# Termo-Relay.net
KiCad netlist of a schematic drawn in EAGLE
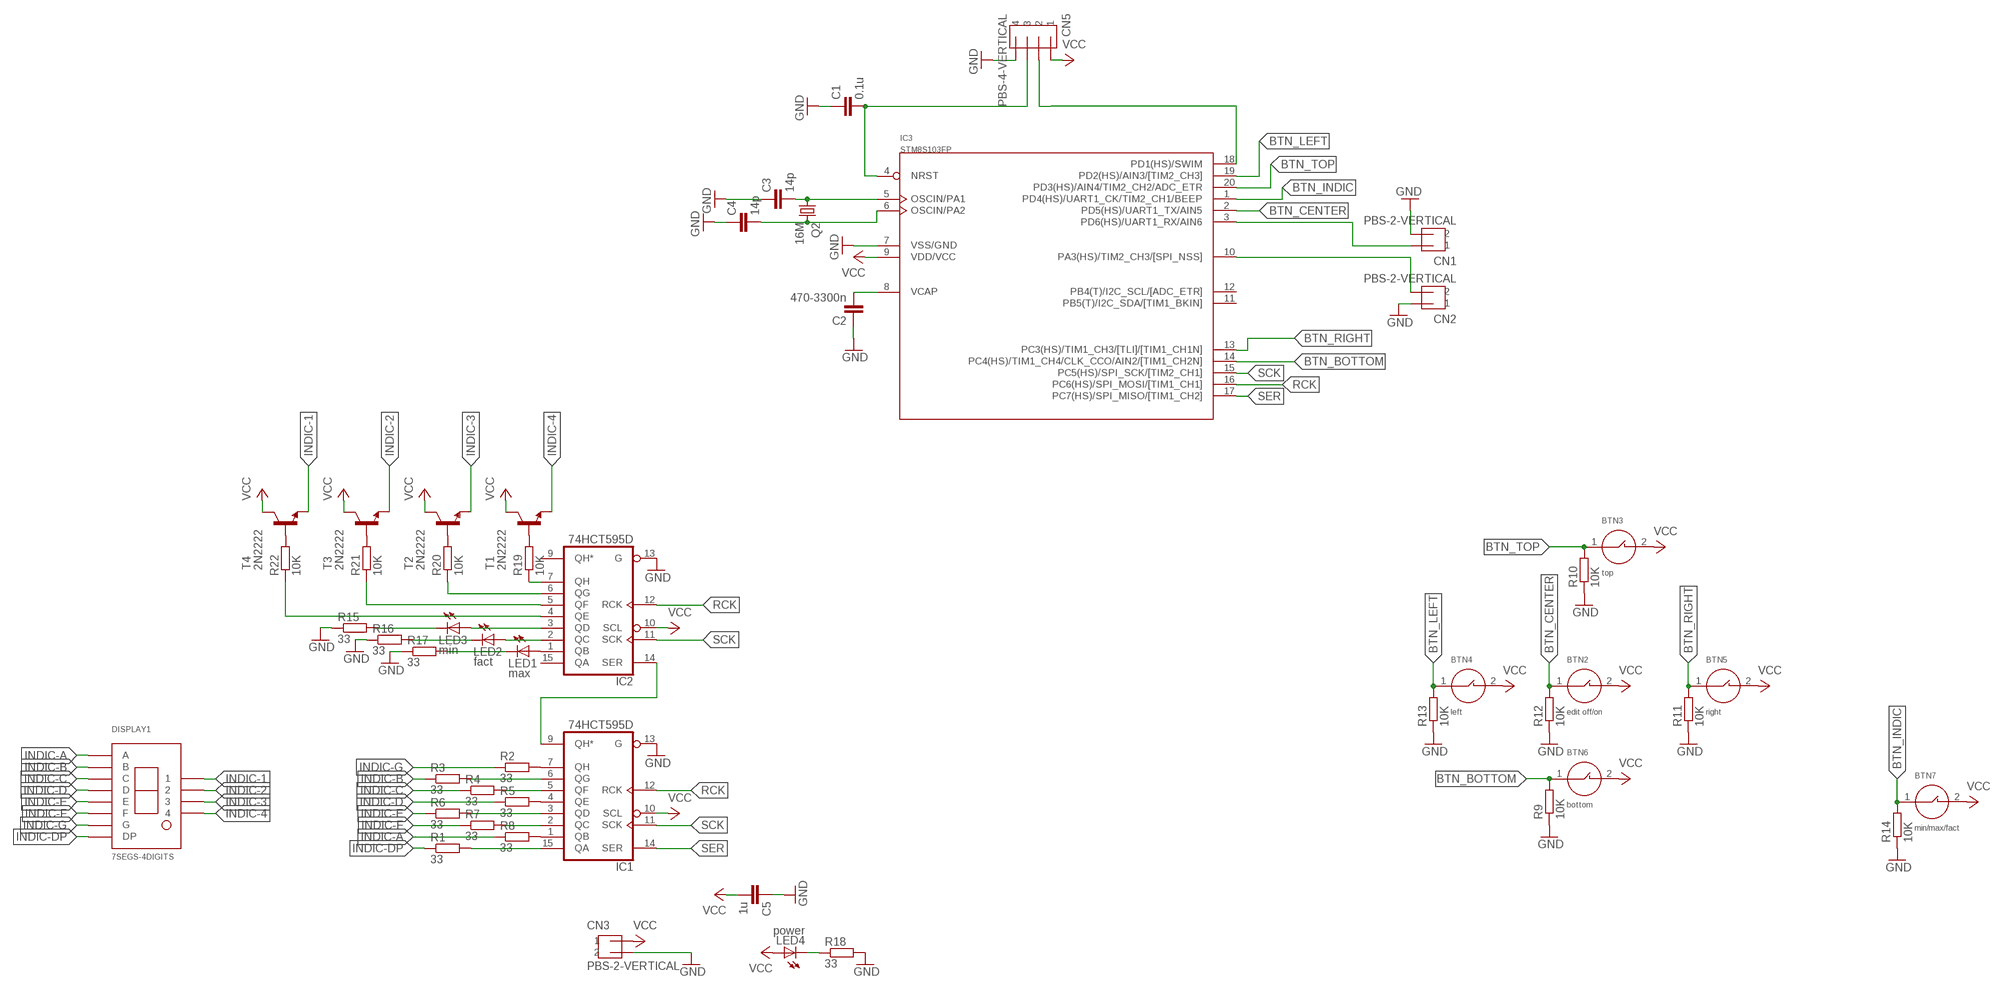
[diagram p0: schematic, sheet 1]

(export (version "E")
  (design (tool "Eeschema 10.0.6"))
  (components
    (comp (ref "BTN2")
      (value "edit off/on")
      (footprint "eagle-import:BTN-6X4-SMD")
      (libsource (lib "eagle-import") (part "BTN-6X4-SMD"))
    )
    (comp (ref "BTN3")
      (value "top")
      (footprint "eagle-import:BTN-6X4-SMD")
      (libsource (lib "eagle-import") (part "BTN-6X4-SMD"))
    )
    (comp (ref "BTN4")
      (value "left")
      (footprint "eagle-import:BTN-6X4-SMD")
      (libsource (lib "eagle-import") (part "BTN-6X4-SMD"))
    )
    (comp (ref "BTN5")
      (value "right")
      (footprint "eagle-import:BTN-6X4-SMD")
      (libsource (lib "eagle-import") (part "BTN-6X4-SMD"))
    )
    (comp (ref "BTN6")
      (value "bottom")
      (footprint "eagle-import:BTN-6X4-SMD")
      (libsource (lib "eagle-import") (part "BTN-6X4-SMD"))
    )
    (comp (ref "BTN7")
      (value "min/max/fact")
      (footprint "eagle-import:BTN-6X4-SMD")
      (libsource (lib "eagle-import") (part "BTN-6X4-SMD"))
    )
    (comp (ref "C1")
      (value "0.1u")
      (footprint "eagle-import:C0603")
      (libsource (lib "eagle-import") (part "C-EUC0603"))
    )
    (comp (ref "C2")
      (value "470-3300n")
      (footprint "eagle-import:C0603")
      (libsource (lib "eagle-import") (part "C-EUC0603"))
    )
    (comp (ref "C3")
      (value "14p")
      (footprint "eagle-import:C0603")
      (libsource (lib "eagle-import") (part "C-EUC0603"))
    )
    (comp (ref "C4")
      (value "14p")
      (footprint "eagle-import:C0603")
      (libsource (lib "eagle-import") (part "C-EUC0603"))
    )
    (comp (ref "C5")
      (value "1u")
      (footprint "eagle-import:C0603")
      (libsource (lib "eagle-import") (part "C-EUC0603"))
    )
    (comp (ref "CN1")
      (value "PBS-2-VERTICAL")
      (footprint "eagle-import:PBS-2-VERTICAL")
      (libsource (lib "eagle-import") (part "PBS-2-VERTICAL"))
    )
    (comp (ref "CN2")
      (value "PBS-2-VERTICAL")
      (footprint "eagle-import:PBS-2-VERTICAL")
      (libsource (lib "eagle-import") (part "PBS-2-VERTICAL"))
    )
    (comp (ref "CN3")
      (value "PBS-2-VERTICAL")
      (footprint "eagle-import:PBS-2-VERTICAL")
      (libsource (lib "eagle-import") (part "PBS-2-VERTICAL"))
    )
    (comp (ref "CN5")
      (value "PBS-4-VERTICAL")
      (footprint "eagle-import:PBS-4-VERTICAL")
      (libsource (lib "eagle-import") (part "PBS-4-VERTICAL"))
    )
    (comp (ref "DISPLAY1")
      (value "7SEGS-4DIGITS")
      (footprint "eagle-import:7SEG-4DIGITS")
      (libsource (lib "eagle-import") (part "7SEGS-4DIGITS"))
    )
    (comp (ref "IC1")
      (value "74HCT595D")
      (footprint "eagle-import:SO16")
      (libsource (lib "eagle-import") (part "74595DHCT"))
    )
    (comp (ref "IC2")
      (value "74HCT595D")
      (footprint "eagle-import:SO16")
      (libsource (lib "eagle-import") (part "74595DHCT"))
    )
    (comp (ref "IC3")
      (value "STM8S103FP")
      (footprint "eagle-import:TSSOP20")
      (libsource (lib "eagle-import") (part "STM8S103FP"))
    )
    (comp (ref "LED1")
      (value "max")
      (footprint "eagle-import:LED3MM")
      (libsource (lib "eagle-import") (part "LED3MM"))
    )
    (comp (ref "LED2")
      (value "fact")
      (footprint "eagle-import:LED3MM")
      (libsource (lib "eagle-import") (part "LED3MM"))
    )
    (comp (ref "LED3")
      (value "min")
      (footprint "eagle-import:LED3MM")
      (libsource (lib "eagle-import") (part "LED3MM"))
    )
    (comp (ref "LED4")
      (value "power")
      (footprint "eagle-import:LED3MM")
      (libsource (lib "eagle-import") (part "LED3MM"))
    )
    (comp (ref "Q2")
      (value "16M")
      (footprint "eagle-import:HC49GW")
      (libsource (lib "eagle-import") (part "CRYSTALHC49GW"))
    )
    (comp (ref "R1")
      (value "33")
      (footprint "eagle-import:R0603")
      (libsource (lib "eagle-import") (part "R-EU_R0603"))
    )
    (comp (ref "R2")
      (value "33")
      (footprint "eagle-import:R0603")
      (libsource (lib "eagle-import") (part "R-EU_R0603"))
    )
    (comp (ref "R3")
      (value "33")
      (footprint "eagle-import:R0603")
      (libsource (lib "eagle-import") (part "R-EU_R0603"))
    )
    (comp (ref "R4")
      (value "33")
      (footprint "eagle-import:R0603")
      (libsource (lib "eagle-import") (part "R-EU_R0603"))
    )
    (comp (ref "R5")
      (value "33")
      (footprint "eagle-import:R0603")
      (libsource (lib "eagle-import") (part "R-EU_R0603"))
    )
    (comp (ref "R6")
      (value "33")
      (footprint "eagle-import:R0603")
      (libsource (lib "eagle-import") (part "R-EU_R0603"))
    )
    (comp (ref "R7")
      (value "33")
      (footprint "eagle-import:R0603")
      (libsource (lib "eagle-import") (part "R-EU_R0603"))
    )
    (comp (ref "R8")
      (value "33")
      (footprint "eagle-import:R0603")
      (libsource (lib "eagle-import") (part "R-EU_R0603"))
    )
    (comp (ref "R9")
      (value "10K")
      (footprint "eagle-import:R0603")
      (libsource (lib "eagle-import") (part "R-EU_R0603"))
    )
    (comp (ref "R10")
      (value "10K")
      (footprint "eagle-import:R0603")
      (libsource (lib "eagle-import") (part "R-EU_R0603"))
    )
    (comp (ref "R11")
      (value "10K")
      (footprint "eagle-import:R0603")
      (libsource (lib "eagle-import") (part "R-EU_R0603"))
    )
    (comp (ref "R12")
      (value "10K")
      (footprint "eagle-import:R0603")
      (libsource (lib "eagle-import") (part "R-EU_R0603"))
    )
    (comp (ref "R13")
      (value "10K")
      (footprint "eagle-import:R0603")
      (libsource (lib "eagle-import") (part "R-EU_R0603"))
    )
    (comp (ref "R14")
      (value "10K")
      (footprint "eagle-import:R0603")
      (libsource (lib "eagle-import") (part "R-EU_R0603"))
    )
    (comp (ref "R15")
      (value "33")
      (footprint "eagle-import:R0603")
      (libsource (lib "eagle-import") (part "R-EU_R0603"))
    )
    (comp (ref "R16")
      (value "33")
      (footprint "eagle-import:R0603")
      (libsource (lib "eagle-import") (part "R-EU_R0603"))
    )
    (comp (ref "R17")
      (value "33")
      (footprint "eagle-import:R0603")
      (libsource (lib "eagle-import") (part "R-EU_R0603"))
    )
    (comp (ref "R18")
      (value "33")
      (footprint "eagle-import:R0603")
      (libsource (lib "eagle-import") (part "R-EU_R0603"))
    )
    (comp (ref "R19")
      (value "10K")
      (footprint "eagle-import:R0603")
      (libsource (lib "eagle-import") (part "R-EU_R0603"))
    )
    (comp (ref "R20")
      (value "10K")
      (footprint "eagle-import:R0603")
      (libsource (lib "eagle-import") (part "R-EU_R0603"))
    )
    (comp (ref "R21")
      (value "10K")
      (footprint "eagle-import:R0603")
      (libsource (lib "eagle-import") (part "R-EU_R0603"))
    )
    (comp (ref "R22")
      (value "10K")
      (footprint "eagle-import:R0603")
      (libsource (lib "eagle-import") (part "R-EU_R0603"))
    )
    (comp (ref "T1")
      (value "2N2222")
      (footprint "eagle-import:SOT23-BEC")
      (libsource (lib "eagle-import") (part "-NPN-SOT23-BECMMBT2222ALT1"))
    )
    (comp (ref "T2")
      (value "2N2222")
      (footprint "eagle-import:SOT23-BEC")
      (libsource (lib "eagle-import") (part "-NPN-SOT23-BECMMBT2222ALT1"))
    )
    (comp (ref "T3")
      (value "2N2222")
      (footprint "eagle-import:SOT23-BEC")
      (libsource (lib "eagle-import") (part "-NPN-SOT23-BECMMBT2222ALT1"))
    )
    (comp (ref "T4")
      (value "2N2222")
      (footprint "eagle-import:SOT23-BEC")
      (libsource (lib "eagle-import") (part "-NPN-SOT23-BECMMBT2222ALT1"))
    )
  )
  (nets
    (net (code "1") (name "BTN_BOTTOM") (class "Default")
      (node (ref "BTN6") (pin "1") (pinfunction "1_1") (pintype "bidirectional"))
      (node (ref "IC3") (pin "14") (pinfunction "PC4(HS)/TIM1_CH4/CLK_CCO/AIN2/[TIM1_CH2N]_14") (pintype "bidirectional"))
      (node (ref "R9") (pin "2") (pinfunction "2_2") (pintype "passive"))
    )
    (net (code "2") (name "BTN_CENTER") (class "Default")
      (node (ref "BTN2") (pin "1") (pinfunction "1_1") (pintype "bidirectional"))
      (node (ref "IC3") (pin "2") (pinfunction "PD5(HS)/UART1_TX/AIN5_2") (pintype "bidirectional"))
      (node (ref "R12") (pin "2") (pinfunction "2_2") (pintype "passive"))
    )
    (net (code "3") (name "BTN_INDIC") (class "Default")
      (node (ref "BTN7") (pin "1") (pinfunction "1_1") (pintype "bidirectional"))
      (node (ref "IC3") (pin "1") (pinfunction "PD4(HS)/UART1_CK/TIM2_CH1/BEEP_1") (pintype "bidirectional"))
      (node (ref "R14") (pin "2") (pinfunction "2_2") (pintype "passive"))
    )
    (net (code "4") (name "BTN_LEFT") (class "Default")
      (node (ref "BTN4") (pin "1") (pinfunction "1_1") (pintype "bidirectional"))
      (node (ref "IC3") (pin "19") (pinfunction "PD2(HS)/AIN3/[TIM2_CH3]_19") (pintype "bidirectional"))
      (node (ref "R13") (pin "2") (pinfunction "2_2") (pintype "passive"))
    )
    (net (code "5") (name "BTN_RIGHT") (class "Default")
      (node (ref "BTN5") (pin "1") (pinfunction "1_1") (pintype "bidirectional"))
      (node (ref "IC3") (pin "13") (pinfunction "PC3(HS)/TIM1_CH3/[TLI]/[TIM1_CH1N]_13") (pintype "bidirectional"))
      (node (ref "R11") (pin "2") (pinfunction "2_2") (pintype "passive"))
    )
    (net (code "6") (name "BTN_TOP") (class "Default")
      (node (ref "BTN3") (pin "1") (pinfunction "1_1") (pintype "bidirectional"))
      (node (ref "IC3") (pin "20") (pinfunction "PD3(HS)/AIN4/TIM2_CH2/ADC_ETR_20") (pintype "bidirectional"))
      (node (ref "R10") (pin "2") (pinfunction "2_2") (pintype "passive"))
    )
    (net (code "7") (name "GND") (class "Default")
      (node (ref "C1") (pin "1") (pinfunction "1_1") (pintype "passive"))
      (node (ref "C2") (pin "1") (pinfunction "1_1") (pintype "passive"))
      (node (ref "C3") (pin "1") (pinfunction "1_1") (pintype "passive"))
      (node (ref "C4") (pin "1") (pinfunction "1_1") (pintype "passive"))
      (node (ref "C5") (pin "1") (pinfunction "1_1") (pintype "passive"))
      (node (ref "CN1") (pin "P$2") (pinfunction "2_P$2") (pintype "bidirectional"))
      (node (ref "CN2") (pin "P$1") (pinfunction "1_P$1") (pintype "bidirectional"))
      (node (ref "CN3") (pin "P$2") (pinfunction "2_P$2") (pintype "bidirectional"))
      (node (ref "CN5") (pin "P$4") (pinfunction "4_P$4") (pintype "bidirectional"))
      (node (ref "IC1") (pin "13") (pinfunction "G_13") (pintype "input"))
      (node (ref "IC2") (pin "13") (pinfunction "G_13") (pintype "input"))
      (node (ref "IC3") (pin "7") (pinfunction "VSS/GND_7") (pintype "power_in"))
      (node (ref "R10") (pin "1") (pinfunction "1_1") (pintype "passive"))
      (node (ref "R11") (pin "1") (pinfunction "1_1") (pintype "passive"))
      (node (ref "R12") (pin "1") (pinfunction "1_1") (pintype "passive"))
      (node (ref "R13") (pin "1") (pinfunction "1_1") (pintype "passive"))
      (node (ref "R14") (pin "1") (pinfunction "1_1") (pintype "passive"))
      (node (ref "R15") (pin "1") (pinfunction "1_1") (pintype "passive"))
      (node (ref "R16") (pin "1") (pinfunction "1_1") (pintype "passive"))
      (node (ref "R17") (pin "1") (pinfunction "1_1") (pintype "passive"))
      (node (ref "R18") (pin "2") (pinfunction "2_2") (pintype "passive"))
      (node (ref "R9") (pin "1") (pinfunction "1_1") (pintype "passive"))
    )
    (net (code "8") (name "INDIC-1") (class "Default")
      (node (ref "DISPLAY1") (pin "1") (pinfunction "1_1") (pintype "bidirectional"))
      (node (ref "T4") (pin "E") (pinfunction "E_E") (pintype "passive"))
    )
    (net (code "9") (name "INDIC-2") (class "Default")
      (node (ref "DISPLAY1") (pin "2") (pinfunction "2_2") (pintype "bidirectional"))
      (node (ref "T3") (pin "E") (pinfunction "E_E") (pintype "passive"))
    )
    (net (code "10") (name "INDIC-3") (class "Default")
      (node (ref "DISPLAY1") (pin "3") (pinfunction "3_3") (pintype "bidirectional"))
      (node (ref "T2") (pin "E") (pinfunction "E_E") (pintype "passive"))
    )
    (net (code "11") (name "INDIC-4") (class "Default")
      (node (ref "DISPLAY1") (pin "4") (pinfunction "4_4") (pintype "bidirectional"))
      (node (ref "T1") (pin "E") (pinfunction "E_E") (pintype "passive"))
    )
    (net (code "12") (name "INDIC-A") (class "Default")
      (node (ref "DISPLAY1") (pin "A") (pinfunction "A_A") (pintype "bidirectional"))
      (node (ref "R8") (pin "1") (pinfunction "1_1") (pintype "passive"))
    )
    (net (code "13") (name "INDIC-B") (class "Default")
      (node (ref "DISPLAY1") (pin "B") (pinfunction "B_B") (pintype "bidirectional"))
      (node (ref "R3") (pin "1") (pinfunction "1_1") (pintype "passive"))
    )
    (net (code "14") (name "INDIC-C") (class "Default")
      (node (ref "DISPLAY1") (pin "C") (pinfunction "C_C") (pintype "bidirectional"))
      (node (ref "R4") (pin "1") (pinfunction "1_1") (pintype "passive"))
    )
    (net (code "15") (name "INDIC-D") (class "Default")
      (node (ref "DISPLAY1") (pin "D") (pinfunction "D_D") (pintype "bidirectional"))
      (node (ref "R5") (pin "1") (pinfunction "1_1") (pintype "passive"))
    )
    (net (code "16") (name "INDIC-DP") (class "Default")
      (node (ref "DISPLAY1") (pin "DP") (pinfunction "DP_DP") (pintype "bidirectional"))
      (node (ref "R1") (pin "1") (pinfunction "1_1") (pintype "passive"))
    )
    (net (code "17") (name "INDIC-E") (class "Default")
      (node (ref "DISPLAY1") (pin "E") (pinfunction "E_E") (pintype "bidirectional"))
      (node (ref "R6") (pin "1") (pinfunction "1_1") (pintype "passive"))
    )
    (net (code "18") (name "INDIC-F") (class "Default")
      (node (ref "DISPLAY1") (pin "F") (pinfunction "F_F") (pintype "bidirectional"))
      (node (ref "R7") (pin "1") (pinfunction "1_1") (pintype "passive"))
    )
    (net (code "19") (name "INDIC-G") (class "Default")
      (node (ref "DISPLAY1") (pin "G") (pinfunction "G_G") (pintype "bidirectional"))
      (node (ref "R2") (pin "1") (pinfunction "1_1") (pintype "passive"))
    )
    (net (code "20") (name "Net-(CN1-1)") (class "Default")
      (node (ref "CN1") (pin "P$1") (pinfunction "1_P$1") (pintype "bidirectional"))
      (node (ref "IC3") (pin "3") (pinfunction "PD6(HS)/UART1_RX/AIN6_3") (pintype "bidirectional"))
    )
    (net (code "21") (name "Net-(CN2-2)") (class "Default")
      (node (ref "CN2") (pin "P$2") (pinfunction "2_P$2") (pintype "bidirectional"))
      (node (ref "IC3") (pin "10") (pinfunction "PA3(HS)/TIM2_CH3/[SPI_NSS]_10") (pintype "bidirectional"))
    )
    (net (code "22") (name "Net-(CN5-2)") (class "Default")
      (node (ref "CN5") (pin "P$2") (pinfunction "2_P$2") (pintype "bidirectional"))
      (node (ref "IC3") (pin "18") (pinfunction "PD1(HS)/SWIM_18") (pintype "bidirectional"))
    )
    (net (code "23") (name "Net-(CN5-3)") (class "Default")
      (node (ref "C1") (pin "2") (pinfunction "2_2") (pintype "passive"))
      (node (ref "CN5") (pin "P$3") (pinfunction "3_P$3") (pintype "bidirectional"))
      (node (ref "IC3") (pin "4") (pinfunction "NRST_4") (pintype "bidirectional"))
    )
    (net (code "24") (name "Net-(IC1A-QA)") (class "Default")
      (node (ref "IC1") (pin "15") (pinfunction "QA_15") (pintype "tri_state"))
      (node (ref "R1") (pin "2") (pinfunction "2_2") (pintype "passive"))
    )
    (net (code "25") (name "Net-(IC1A-QB)") (class "Default")
      (node (ref "IC1") (pin "1") (pinfunction "QB_1") (pintype "tri_state"))
      (node (ref "R8") (pin "2") (pinfunction "2_2") (pintype "passive"))
    )
    (net (code "26") (name "Net-(IC1A-QC)") (class "Default")
      (node (ref "IC1") (pin "2") (pinfunction "QC_2") (pintype "tri_state"))
      (node (ref "R7") (pin "2") (pinfunction "2_2") (pintype "passive"))
    )
    (net (code "27") (name "Net-(IC1A-QD)") (class "Default")
      (node (ref "IC1") (pin "3") (pinfunction "QD_3") (pintype "tri_state"))
      (node (ref "R6") (pin "2") (pinfunction "2_2") (pintype "passive"))
    )
    (net (code "28") (name "Net-(IC1A-QE)") (class "Default")
      (node (ref "IC1") (pin "4") (pinfunction "QE_4") (pintype "tri_state"))
      (node (ref "R5") (pin "2") (pinfunction "2_2") (pintype "passive"))
    )
    (net (code "29") (name "Net-(IC1A-QF)") (class "Default")
      (node (ref "IC1") (pin "5") (pinfunction "QF_5") (pintype "tri_state"))
      (node (ref "R4") (pin "2") (pinfunction "2_2") (pintype "passive"))
    )
    (net (code "30") (name "Net-(IC1A-QG)") (class "Default")
      (node (ref "IC1") (pin "6") (pinfunction "QG_6") (pintype "tri_state"))
      (node (ref "R3") (pin "2") (pinfunction "2_2") (pintype "passive"))
    )
    (net (code "31") (name "Net-(IC1A-QH)") (class "Default")
      (node (ref "IC1") (pin "7") (pinfunction "QH_7") (pintype "tri_state"))
      (node (ref "R2") (pin "2") (pinfunction "2_2") (pintype "passive"))
    )
    (net (code "32") (name "Net-(IC1A-QH*)") (class "Default")
      (node (ref "IC1") (pin "9") (pinfunction "QH*_9") (pintype "tri_state"))
      (node (ref "IC2") (pin "14") (pinfunction "SER_14") (pintype "input"))
    )
    (net (code "33") (name "Net-(IC2A-QB)") (class "Default")
      (node (ref "IC2") (pin "1") (pinfunction "QB_1") (pintype "tri_state"))
      (node (ref "LED1") (pin "A") (pinfunction "A_A") (pintype "passive"))
    )
    (net (code "34") (name "Net-(IC2A-QC)") (class "Default")
      (node (ref "IC2") (pin "2") (pinfunction "QC_2") (pintype "tri_state"))
      (node (ref "LED2") (pin "A") (pinfunction "A_A") (pintype "passive"))
    )
    (net (code "35") (name "Net-(IC2A-QD)") (class "Default")
      (node (ref "IC2") (pin "3") (pinfunction "QD_3") (pintype "tri_state"))
      (node (ref "LED3") (pin "A") (pinfunction "A_A") (pintype "passive"))
    )
    (net (code "36") (name "Net-(IC2A-QE)") (class "Default")
      (node (ref "IC2") (pin "4") (pinfunction "QE_4") (pintype "tri_state"))
      (node (ref "R22") (pin "1") (pinfunction "1_1") (pintype "passive"))
    )
    (net (code "37") (name "Net-(IC2A-QF)") (class "Default")
      (node (ref "IC2") (pin "5") (pinfunction "QF_5") (pintype "tri_state"))
      (node (ref "R21") (pin "1") (pinfunction "1_1") (pintype "passive"))
    )
    (net (code "38") (name "Net-(IC2A-QG)") (class "Default")
      (node (ref "IC2") (pin "6") (pinfunction "QG_6") (pintype "tri_state"))
      (node (ref "R20") (pin "1") (pinfunction "1_1") (pintype "passive"))
    )
    (net (code "39") (name "Net-(IC2A-QH)") (class "Default")
      (node (ref "IC2") (pin "7") (pinfunction "QH_7") (pintype "tri_state"))
      (node (ref "R19") (pin "1") (pinfunction "1_1") (pintype "passive"))
    )
    (net (code "40") (name "Net-(IC3-OSCIN{slash}PA1)") (class "Default")
      (node (ref "C3") (pin "2") (pinfunction "2_2") (pintype "passive"))
      (node (ref "IC3") (pin "5") (pinfunction "OSCIN/PA1_5") (pintype "bidirectional"))
      (node (ref "Q2") (pin "1") (pinfunction "1_1") (pintype "passive"))
    )
    (net (code "41") (name "Net-(IC3-OSCIN{slash}PA2)") (class "Default")
      (node (ref "C4") (pin "2") (pinfunction "2_2") (pintype "passive"))
      (node (ref "IC3") (pin "6") (pinfunction "OSCIN/PA2_6") (pintype "bidirectional"))
      (node (ref "Q2") (pin "2") (pinfunction "2_2") (pintype "passive"))
    )
    (net (code "42") (name "Net-(IC3-VCAP)") (class "Default")
      (node (ref "C2") (pin "2") (pinfunction "2_2") (pintype "passive"))
      (node (ref "IC3") (pin "8") (pinfunction "VCAP_8") (pintype "power_in"))
    )
    (net (code "43") (name "Net-(LED1-C)") (class "Default")
      (node (ref "LED1") (pin "K") (pinfunction "C_K") (pintype "passive"))
      (node (ref "R17") (pin "2") (pinfunction "2_2") (pintype "passive"))
    )
    (net (code "44") (name "Net-(LED2-C)") (class "Default")
      (node (ref "LED2") (pin "K") (pinfunction "C_K") (pintype "passive"))
      (node (ref "R16") (pin "2") (pinfunction "2_2") (pintype "passive"))
    )
    (net (code "45") (name "Net-(LED3-C)") (class "Default")
      (node (ref "LED3") (pin "K") (pinfunction "C_K") (pintype "passive"))
      (node (ref "R15") (pin "2") (pinfunction "2_2") (pintype "passive"))
    )
    (net (code "46") (name "Net-(LED4-C)") (class "Default")
      (node (ref "LED4") (pin "K") (pinfunction "C_K") (pintype "passive"))
      (node (ref "R18") (pin "1") (pinfunction "1_1") (pintype "passive"))
    )
    (net (code "47") (name "Net-(R19-Pad2)") (class "Default")
      (node (ref "R19") (pin "2") (pinfunction "2_2") (pintype "passive"))
      (node (ref "T1") (pin "B") (pinfunction "B_B") (pintype "passive"))
    )
    (net (code "48") (name "Net-(R20-Pad2)") (class "Default")
      (node (ref "R20") (pin "2") (pinfunction "2_2") (pintype "passive"))
      (node (ref "T2") (pin "B") (pinfunction "B_B") (pintype "passive"))
    )
    (net (code "49") (name "Net-(R21-Pad2)") (class "Default")
      (node (ref "R21") (pin "2") (pinfunction "2_2") (pintype "passive"))
      (node (ref "T3") (pin "B") (pinfunction "B_B") (pintype "passive"))
    )
    (net (code "50") (name "Net-(R22-Pad2)") (class "Default")
      (node (ref "R22") (pin "2") (pinfunction "2_2") (pintype "passive"))
      (node (ref "T4") (pin "B") (pinfunction "B_B") (pintype "passive"))
    )
    (net (code "51") (name "RCK") (class "Default")
      (node (ref "IC1") (pin "12") (pinfunction "RCK_12") (pintype "input"))
      (node (ref "IC2") (pin "12") (pinfunction "RCK_12") (pintype "input"))
      (node (ref "IC3") (pin "16") (pinfunction "PC6(HS)/SPI_MOSI/[TIM1_CH1]_16") (pintype "bidirectional"))
    )
    (net (code "52") (name "SCK") (class "Default")
      (node (ref "IC1") (pin "11") (pinfunction "SCK_11") (pintype "input"))
      (node (ref "IC2") (pin "11") (pinfunction "SCK_11") (pintype "input"))
      (node (ref "IC3") (pin "15") (pinfunction "PC5(HS)/SPI_SCK/[TIM2_CH1]_15") (pintype "bidirectional"))
    )
    (net (code "53") (name "SER") (class "Default")
      (node (ref "IC1") (pin "14") (pinfunction "SER_14") (pintype "input"))
      (node (ref "IC3") (pin "17") (pinfunction "PC7(HS)/SPI_MISO/[TIM1_CH2]_17") (pintype "bidirectional"))
    )
    (net (code "54") (name "VCC") (class "Default")
      (node (ref "BTN2") (pin "2") (pinfunction "2_2") (pintype "bidirectional"))
      (node (ref "BTN3") (pin "2") (pinfunction "2_2") (pintype "bidirectional"))
      (node (ref "BTN4") (pin "2") (pinfunction "2_2") (pintype "bidirectional"))
      (node (ref "BTN5") (pin "2") (pinfunction "2_2") (pintype "bidirectional"))
      (node (ref "BTN6") (pin "2") (pinfunction "2_2") (pintype "bidirectional"))
      (node (ref "BTN7") (pin "2") (pinfunction "2_2") (pintype "bidirectional"))
      (node (ref "C5") (pin "2") (pinfunction "2_2") (pintype "passive"))
      (node (ref "CN3") (pin "P$1") (pinfunction "1_P$1") (pintype "bidirectional"))
      (node (ref "CN5") (pin "P$1") (pinfunction "1_P$1") (pintype "bidirectional"))
      (node (ref "IC1") (pin "10") (pinfunction "SCL_10") (pintype "input"))
      (node (ref "IC2") (pin "10") (pinfunction "SCL_10") (pintype "input"))
      (node (ref "IC3") (pin "9") (pinfunction "VDD/VCC_9") (pintype "power_in"))
      (node (ref "LED4") (pin "A") (pinfunction "A_A") (pintype "passive"))
      (node (ref "T1") (pin "C") (pinfunction "C_C") (pintype "passive"))
      (node (ref "T2") (pin "C") (pinfunction "C_C") (pintype "passive"))
      (node (ref "T3") (pin "C") (pinfunction "C_C") (pintype "passive"))
      (node (ref "T4") (pin "C") (pinfunction "C_C") (pintype "passive"))
    )
    (net (code "55") (name "unconnected-(IC2A-QA-Pad15)") (class "Default")
      (node (ref "IC2") (pin "15") (pinfunction "QA_15") (pintype "tri_state"))
    )
    (net (code "56") (name "unconnected-(IC2A-QH*-Pad9)") (class "Default")
      (node (ref "IC2") (pin "9") (pinfunction "QH*_9") (pintype "tri_state"))
    )
    (net (code "57") (name "unconnected-(IC3-PB4(T){slash}I2C_SCL{slash}[ADC_ETR]-Pad12)") (class "Default")
      (node (ref "IC3") (pin "12") (pinfunction "PB4(T)/I2C_SCL/[ADC_ETR]_12") (pintype "bidirectional"))
    )
    (net (code "58") (name "unconnected-(IC3-PB5(T){slash}I2C_SDA{slash}[TIM1_BKIN]-Pad11)") (class "Default")
      (node (ref "IC3") (pin "11") (pinfunction "PB5(T)/I2C_SDA/[TIM1_BKIN]_11") (pintype "bidirectional"))
    )
  )
)
